# LED_Board.net
KiCad netlist of a schematic drawn in EAGLE
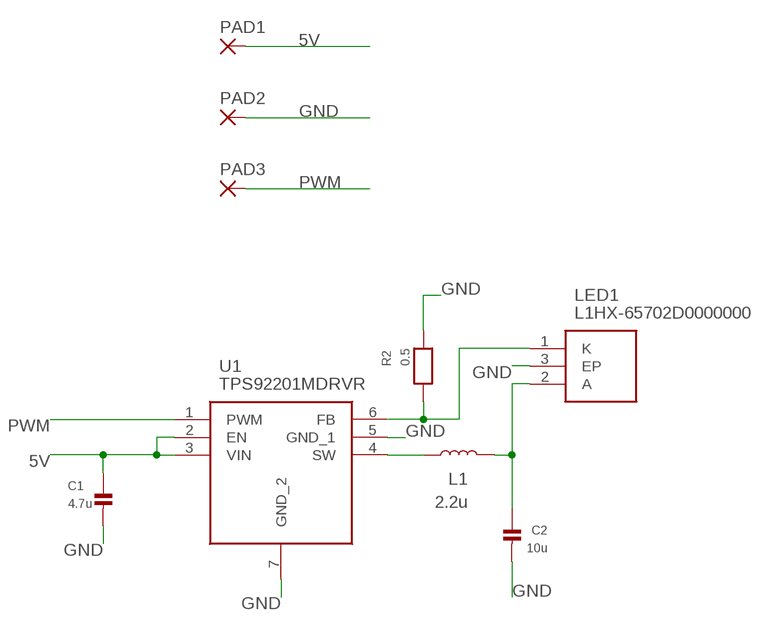
[diagram p0: schematic, sheet 1]

(export (version "E")
  (design (tool "Eeschema 10.0.6"))
  (components
    (comp (ref "C1")
      (value "4.7u")
      (footprint "eagle-import:0805")
      (libsource (lib "eagle-import") (part "CAP_CERAMIC0805"))
    )
    (comp (ref "C2")
      (value "10u")
      (footprint "eagle-import:0805")
      (libsource (lib "eagle-import") (part "CAP_CERAMIC0805"))
    )
    (comp (ref "L1")
      (value "2.2u")
      (footprint "eagle-import:1008(2520)")
      (libsource (lib "eagle-import") (part "2.2μH"))
    )
    (comp (ref "LED1")
      (value "L1HX-65702D0000000")
      (footprint "eagle-import:L1HX65702D0000000")
      (fields (field (name "MOUSER_PART_NUMBER") "997-L1HX65702D00"))
      (libsource (lib "eagle-import") (part "L1HX-65702D0000000"))
    )
    (comp (ref "PAD1")
      (value "SMD2")
      (footprint "eagle-import:SMD1,27-2,54")
      (libsource (lib "eagle-import") (part "SMD2"))
    )
    (comp (ref "PAD2")
      (value "SMD2")
      (footprint "eagle-import:SMD1,27-2,54")
      (libsource (lib "eagle-import") (part "SMD2"))
    )
    (comp (ref "PAD3")
      (value "SMD2")
      (footprint "eagle-import:SMD1,27-2,54")
      (libsource (lib "eagle-import") (part "SMD2"))
    )
    (comp (ref "R2")
      (value "0.5")
      (footprint "eagle-import:R0603")
      (libsource (lib "eagle-import") (part "RESISTOR_R0603"))
    )
    (comp (ref "U1")
      (value "TPS92201MDRVR")
      (footprint "eagle-import:SON65P200X200X80-7N")
      (fields (field (name "MOUSER_PART_NUMBER") "595-TPS92201MDRVR"))
      (libsource (lib "eagle-import") (part "TPS92201MDRVR"))
    )
  )
  (nets
    (net (code "1") (name "/5V") (class "Default")
      (node (ref "C1") (pin "1") (pinfunction "P$1_1") (pintype "passive"))
      (node (ref "PAD1") (pin "1") (pinfunction "P_1") (pintype "passive"))
      (node (ref "U1") (pin "2") (pinfunction "EN_2") (pintype "bidirectional"))
      (node (ref "U1") (pin "3") (pinfunction "VIN_3") (pintype "bidirectional"))
    )
    (net (code "2") (name "/GND") (class "Default")
      (node (ref "C1") (pin "2") (pinfunction "P$2_2") (pintype "passive"))
      (node (ref "C2") (pin "2") (pinfunction "P$2_2") (pintype "passive"))
      (node (ref "LED1") (pin "3") (pinfunction "EP_3") (pintype "bidirectional"))
      (node (ref "PAD2") (pin "1") (pinfunction "P_1") (pintype "passive"))
      (node (ref "R2") (pin "2") (pinfunction "2_2") (pintype "passive"))
      (node (ref "U1") (pin "5") (pinfunction "GND_1_5") (pintype "bidirectional"))
      (node (ref "U1") (pin "7") (pinfunction "GND_2_7") (pintype "bidirectional"))
    )
    (net (code "3") (name "/PWM") (class "Default")
      (node (ref "PAD3") (pin "1") (pinfunction "P_1") (pintype "passive"))
      (node (ref "U1") (pin "1") (pinfunction "PWM_1") (pintype "bidirectional"))
    )
    (net (code "4") (name "Net-(C2-P$1)") (class "Default")
      (node (ref "C2") (pin "1") (pinfunction "P$1_1") (pintype "passive"))
      (node (ref "L1") (pin "2") (pinfunction "2_2") (pintype "passive"))
      (node (ref "LED1") (pin "2") (pinfunction "A_2") (pintype "bidirectional"))
    )
    (net (code "5") (name "Net-(LED1-K)") (class "Default")
      (node (ref "LED1") (pin "1") (pinfunction "K_1") (pintype "bidirectional"))
      (node (ref "R2") (pin "1") (pinfunction "1_1") (pintype "passive"))
      (node (ref "U1") (pin "6") (pinfunction "FB_6") (pintype "bidirectional"))
    )
    (net (code "6") (name "Net-(U1-SW)") (class "Default")
      (node (ref "L1") (pin "1") (pinfunction "1_1") (pintype "passive"))
      (node (ref "U1") (pin "4") (pinfunction "SW_4") (pintype "bidirectional"))
    )
  )
)
